# MicroPumpPCB.net
KiCad netlist of a schematic drawn in EAGLE
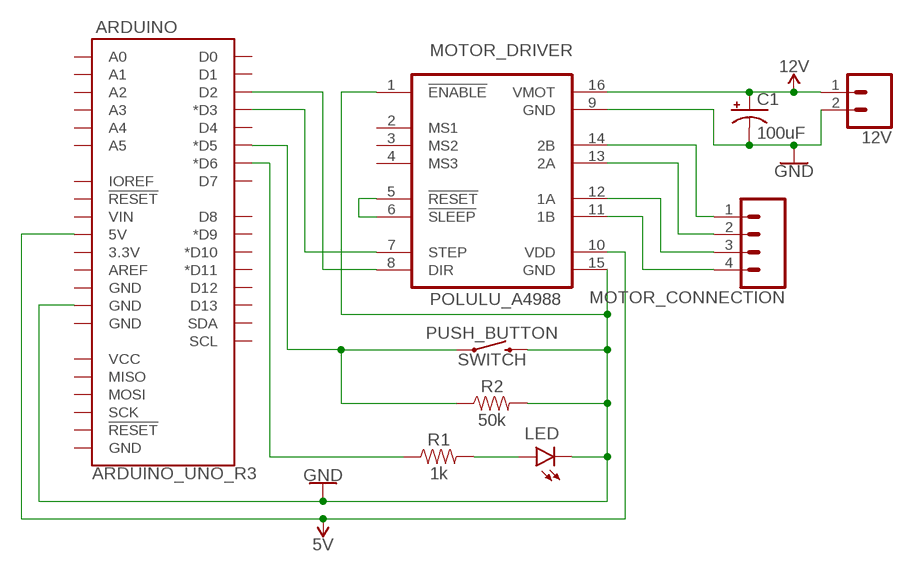
[diagram p0: schematic, sheet 1]

(export (version "E")
  (design (tool "Eeschema 10.0.6"))
  (components
    (comp (ref "12V")
      (value "CONN_02POLAR")
      (footprint "eagle-import:MOLEX-1X2")
      (libsource (lib "eagle-import") (part "CONN_02POLAR"))
    )
    (comp (ref "ARDUINO")
      (value "ARDUINO_UNO_R3")
      (footprint "eagle-import:ARDUINO_R3")
      (libsource (lib "eagle-import") (part "ARDUINO_UNO_R3"))
    )
    (comp (ref "C1")
      (value "100uF")
      (footprint "eagle-import:CPOL-RADIAL-2.5MM-6.5MM")
      (libsource (lib "eagle-import") (part "100UF-POLAR-RADIAL-2.5MM-25V-20%"))
    )
    (comp (ref "LED")
      (value "LED5MM")
      (footprint "eagle-import:LED_5MM")
      (libsource (lib "eagle-import") (part "LED5MM"))
    )
    (comp (ref "MOTOR_CONNECTION")
      (value "CONN_04")
      (footprint "eagle-import:1X04")
      (libsource (lib "eagle-import") (part "CONN_04"))
    )
    (comp (ref "POLULU_A4988")
      (value "MOTOR_DRIVER")
      (footprint "eagle-import:POLOLULU2128")
      (libsource (lib "eagle-import") (part "POLOLULU2128"))
    )
    (comp (ref "PUSH_BUTTON")
      (value "SWITCH")
      (footprint "eagle-import:TACTILE_SWITCH_PTH_6.0MM")
      (libsource (lib "eagle-import") (part "MOMENTARY-SWITCH-SPST-PTH-6.0MM"))
    )
    (comp (ref "R1")
      (value "1k")
      (footprint "eagle-import:AXIAL-0.3")
      (libsource (lib "eagle-import") (part "1KOHM-HORIZ-1/4W-1%"))
    )
    (comp (ref "R2")
      (value "50k")
      (footprint "eagle-import:AXIAL-0.3")
      (libsource (lib "eagle-import") (part "1KOHM-HORIZ-1/4W-1%"))
    )
  )
  (nets
    (net (code "1") (name "5V") (class "Default")
      (node (ref "ARDUINO") (pin "5V") (pinfunction "5V_5V") (pintype "bidirectional"))
      (node (ref "POLULU_A4988") (pin "10") (pinfunction "VDD_10") (pintype "power_in"))
    )
    (net (code "2") (name "12V") (class "Default")
      (node (ref "12V") (pin "1") (pinfunction "1_1") (pintype "passive"))
      (node (ref "C1") (pin "1") (pinfunction "+_1") (pintype "passive"))
      (node (ref "POLULU_A4988") (pin "16") (pinfunction "VMOT_16") (pintype "power_in"))
    )
    (net (code "3") (name "GND") (class "Default")
      (node (ref "12V") (pin "2") (pinfunction "2_2") (pintype "passive"))
      (node (ref "ARDUINO") (pin "GND@3") (pinfunction "GND_GND@3") (pintype "bidirectional"))
      (node (ref "C1") (pin "2") (pinfunction "-_2") (pintype "passive"))
      (node (ref "LED") (pin "K") (pinfunction "C_K") (pintype "passive"))
      (node (ref "POLULU_A4988") (pin "1") (pinfunction "~{ENABLE}_1") (pintype "input"))
      (node (ref "POLULU_A4988") (pin "15") (pinfunction "GND_15") (pintype "power_in"))
      (node (ref "POLULU_A4988") (pin "9") (pinfunction "GND_9") (pintype "power_in"))
      (node (ref "PUSH_BUTTON") (pin "3") (pinfunction "2_3") (pintype "passive"))
      (node (ref "R2") (pin "P$2") (pinfunction "2_P$2") (pintype "passive"))
    )
    (net (code "4") (name "Net-(ARDUINO-*D3)") (class "Default")
      (node (ref "ARDUINO") (pin "D3") (pinfunction "*D3_D3") (pintype "bidirectional"))
      (node (ref "POLULU_A4988") (pin "7") (pinfunction "STEP_7") (pintype "input"))
    )
    (net (code "5") (name "Net-(ARDUINO-*D5)") (class "Default")
      (node (ref "ARDUINO") (pin "D5") (pinfunction "*D5_D5") (pintype "bidirectional"))
      (node (ref "PUSH_BUTTON") (pin "1") (pinfunction "1_1") (pintype "passive"))
      (node (ref "R2") (pin "P$1") (pinfunction "1_P$1") (pintype "passive"))
    )
    (net (code "6") (name "Net-(ARDUINO-*D6)") (class "Default")
      (node (ref "ARDUINO") (pin "D6") (pinfunction "*D6_D6") (pintype "bidirectional"))
      (node (ref "R1") (pin "P$1") (pinfunction "1_P$1") (pintype "passive"))
    )
    (net (code "7") (name "Net-(POLULU_A4988-1A)") (class "Default")
      (node (ref "MOTOR_CONNECTION") (pin "3") (pinfunction "3_3") (pintype "passive"))
      (node (ref "POLULU_A4988") (pin "12") (pinfunction "1A_12") (pintype "output"))
    )
    (net (code "8") (name "Net-(POLULU_A4988-1B)") (class "Default")
      (node (ref "MOTOR_CONNECTION") (pin "4") (pinfunction "4_4") (pintype "passive"))
      (node (ref "POLULU_A4988") (pin "11") (pinfunction "1B_11") (pintype "output"))
    )
    (net (code "9") (name "Net-(POLULU_A4988-2A)") (class "Default")
      (node (ref "MOTOR_CONNECTION") (pin "2") (pinfunction "2_2") (pintype "passive"))
      (node (ref "POLULU_A4988") (pin "13") (pinfunction "2A_13") (pintype "output"))
    )
    (net (code "10") (name "Net-(POLULU_A4988-2B)") (class "Default")
      (node (ref "MOTOR_CONNECTION") (pin "1") (pinfunction "1_1") (pintype "passive"))
      (node (ref "POLULU_A4988") (pin "14") (pinfunction "2B_14") (pintype "output"))
    )
    (net (code "11") (name "Net-(POLULU_A4988-DIR)") (class "Default")
      (node (ref "ARDUINO") (pin "D2") (pinfunction "D2_D2") (pintype "bidirectional"))
      (node (ref "POLULU_A4988") (pin "8") (pinfunction "DIR_8") (pintype "input"))
    )
    (net (code "12") (name "Net-(POLULU_A4988-~{RESET})") (class "Default")
      (node (ref "POLULU_A4988") (pin "5") (pinfunction "~{RESET}_5") (pintype "input"))
      (node (ref "POLULU_A4988") (pin "6") (pinfunction "~{SLEEP}_6") (pintype "input"))
    )
    (net (code "13") (name "Net-(R1-2)") (class "Default")
      (node (ref "LED") (pin "A") (pinfunction "A_A") (pintype "passive"))
      (node (ref "R1") (pin "P$2") (pinfunction "2_P$2") (pintype "passive"))
    )
    (net (code "14") (name "unconnected-(ARDUINO-*D9-PadD9)") (class "Default")
      (node (ref "ARDUINO") (pin "D9") (pinfunction "*D9_D9") (pintype "bidirectional"))
    )
    (net (code "15") (name "unconnected-(ARDUINO-*D10-PadD10)") (class "Default")
      (node (ref "ARDUINO") (pin "D10") (pinfunction "*D10_D10") (pintype "bidirectional"))
    )
    (net (code "16") (name "unconnected-(ARDUINO-*D11-PadD11)") (class "Default")
      (node (ref "ARDUINO") (pin "D11") (pinfunction "*D11_D11") (pintype "bidirectional"))
    )
    (net (code "17") (name "unconnected-(ARDUINO-GND-PadGND@1)") (class "Default")
      (node (ref "ARDUINO") (pin "GND@1") (pinfunction "GND_GND@1") (pintype "bidirectional"))
    )
    (net (code "18") (name "unconnected-(ARDUINO-GND-PadGND@2)") (class "Default")
      (node (ref "ARDUINO") (pin "GND@2") (pinfunction "GND_GND@2") (pintype "bidirectional"))
    )
    (net (code "19") (name "unconnected-(ARDUINO-GND-PadGND@4)") (class "Default")
      (node (ref "ARDUINO") (pin "GND@4") (pinfunction "GND_GND@4") (pintype "bidirectional"))
    )
    (net (code "20") (name "unconnected-(ARDUINO-Pad3.3V)") (class "Default")
      (node (ref "ARDUINO") (pin "3.3V") (pinfunction "3.3V_3.3V") (pintype "bidirectional"))
    )
    (net (code "21") (name "unconnected-(ARDUINO-PadA0)") (class "Default")
      (node (ref "ARDUINO") (pin "A0") (pinfunction "A0_A0") (pintype "bidirectional"))
    )
    (net (code "22") (name "unconnected-(ARDUINO-PadA1)") (class "Default")
      (node (ref "ARDUINO") (pin "A1") (pinfunction "A1_A1") (pintype "bidirectional"))
    )
    (net (code "23") (name "unconnected-(ARDUINO-PadA2)") (class "Default")
      (node (ref "ARDUINO") (pin "A2") (pinfunction "A2_A2") (pintype "bidirectional"))
    )
    (net (code "24") (name "unconnected-(ARDUINO-PadA3)") (class "Default")
      (node (ref "ARDUINO") (pin "A3") (pinfunction "A3_A3") (pintype "bidirectional"))
    )
    (net (code "25") (name "unconnected-(ARDUINO-PadA4)") (class "Default")
      (node (ref "ARDUINO") (pin "A4") (pinfunction "A4_A4") (pintype "bidirectional"))
    )
    (net (code "26") (name "unconnected-(ARDUINO-PadA5)") (class "Default")
      (node (ref "ARDUINO") (pin "A5") (pinfunction "A5_A5") (pintype "bidirectional"))
    )
    (net (code "27") (name "unconnected-(ARDUINO-PadAREF)") (class "Default")
      (node (ref "ARDUINO") (pin "AREF") (pinfunction "AREF_AREF") (pintype "bidirectional"))
    )
    (net (code "28") (name "unconnected-(ARDUINO-PadD0)") (class "Default")
      (node (ref "ARDUINO") (pin "D0") (pinfunction "D0_D0") (pintype "bidirectional"))
    )
    (net (code "29") (name "unconnected-(ARDUINO-PadD1)") (class "Default")
      (node (ref "ARDUINO") (pin "D1") (pinfunction "D1_D1") (pintype "bidirectional"))
    )
    (net (code "30") (name "unconnected-(ARDUINO-PadD4)") (class "Default")
      (node (ref "ARDUINO") (pin "D4") (pinfunction "D4_D4") (pintype "bidirectional"))
    )
    (net (code "31") (name "unconnected-(ARDUINO-PadD7)") (class "Default")
      (node (ref "ARDUINO") (pin "D7") (pinfunction "D7_D7") (pintype "bidirectional"))
    )
    (net (code "32") (name "unconnected-(ARDUINO-PadD8)") (class "Default")
      (node (ref "ARDUINO") (pin "D8") (pinfunction "D8_D8") (pintype "bidirectional"))
    )
    (net (code "33") (name "unconnected-(ARDUINO-PadD12)") (class "Default")
      (node (ref "ARDUINO") (pin "D12") (pinfunction "D12_D12") (pintype "bidirectional"))
    )
    (net (code "34") (name "unconnected-(ARDUINO-PadD13)") (class "Default")
      (node (ref "ARDUINO") (pin "D13") (pinfunction "D13_D13") (pintype "bidirectional"))
    )
    (net (code "35") (name "unconnected-(ARDUINO-PadIOREF)") (class "Default")
      (node (ref "ARDUINO") (pin "IOREF") (pinfunction "IOREF_IOREF") (pintype "bidirectional"))
    )
    (net (code "36") (name "unconnected-(ARDUINO-PadMISO)") (class "Default")
      (node (ref "ARDUINO") (pin "MISO") (pinfunction "MISO_MISO") (pintype "bidirectional"))
    )
    (net (code "37") (name "unconnected-(ARDUINO-PadMOSI)") (class "Default")
      (node (ref "ARDUINO") (pin "MOSI") (pinfunction "MOSI_MOSI") (pintype "bidirectional"))
    )
    (net (code "38") (name "unconnected-(ARDUINO-PadSCK)") (class "Default")
      (node (ref "ARDUINO") (pin "SCK") (pinfunction "SCK_SCK") (pintype "bidirectional"))
    )
    (net (code "39") (name "unconnected-(ARDUINO-PadSCL)") (class "Default")
      (node (ref "ARDUINO") (pin "SCL") (pinfunction "SCL_SCL") (pintype "bidirectional"))
    )
    (net (code "40") (name "unconnected-(ARDUINO-PadSDA)") (class "Default")
      (node (ref "ARDUINO") (pin "SDA") (pinfunction "SDA_SDA") (pintype "bidirectional"))
    )
    (net (code "41") (name "unconnected-(ARDUINO-PadVCC)") (class "Default")
      (node (ref "ARDUINO") (pin "VCC") (pinfunction "VCC_VCC") (pintype "bidirectional"))
    )
    (net (code "42") (name "unconnected-(ARDUINO-PadVIN)") (class "Default")
      (node (ref "ARDUINO") (pin "VIN") (pinfunction "VIN_VIN") (pintype "bidirectional"))
    )
    (net (code "43") (name "unconnected-(ARDUINO-~{RESET}-PadRESET@1)") (class "Default")
      (node (ref "ARDUINO") (pin "RESET@1") (pinfunction "~{RESET}_RESET@1") (pintype "bidirectional"))
    )
    (net (code "44") (name "unconnected-(ARDUINO-~{RESET}-PadRESET@2)") (class "Default")
      (node (ref "ARDUINO") (pin "RESET@2") (pinfunction "~{RESET}_RESET@2") (pintype "bidirectional"))
    )
    (net (code "45") (name "unconnected-(POLULU_A4988-MS1-Pad2)") (class "Default")
      (node (ref "POLULU_A4988") (pin "2") (pinfunction "MS1_2") (pintype "input"))
    )
    (net (code "46") (name "unconnected-(POLULU_A4988-MS2-Pad3)") (class "Default")
      (node (ref "POLULU_A4988") (pin "3") (pinfunction "MS2_3") (pintype "input"))
    )
    (net (code "47") (name "unconnected-(POLULU_A4988-MS3-Pad4)") (class "Default")
      (node (ref "POLULU_A4988") (pin "4") (pinfunction "MS3_4") (pintype "input"))
    )
  )
)
